# RaspberyConnector.net
KiCad netlist of a schematic drawn in Altium Designer
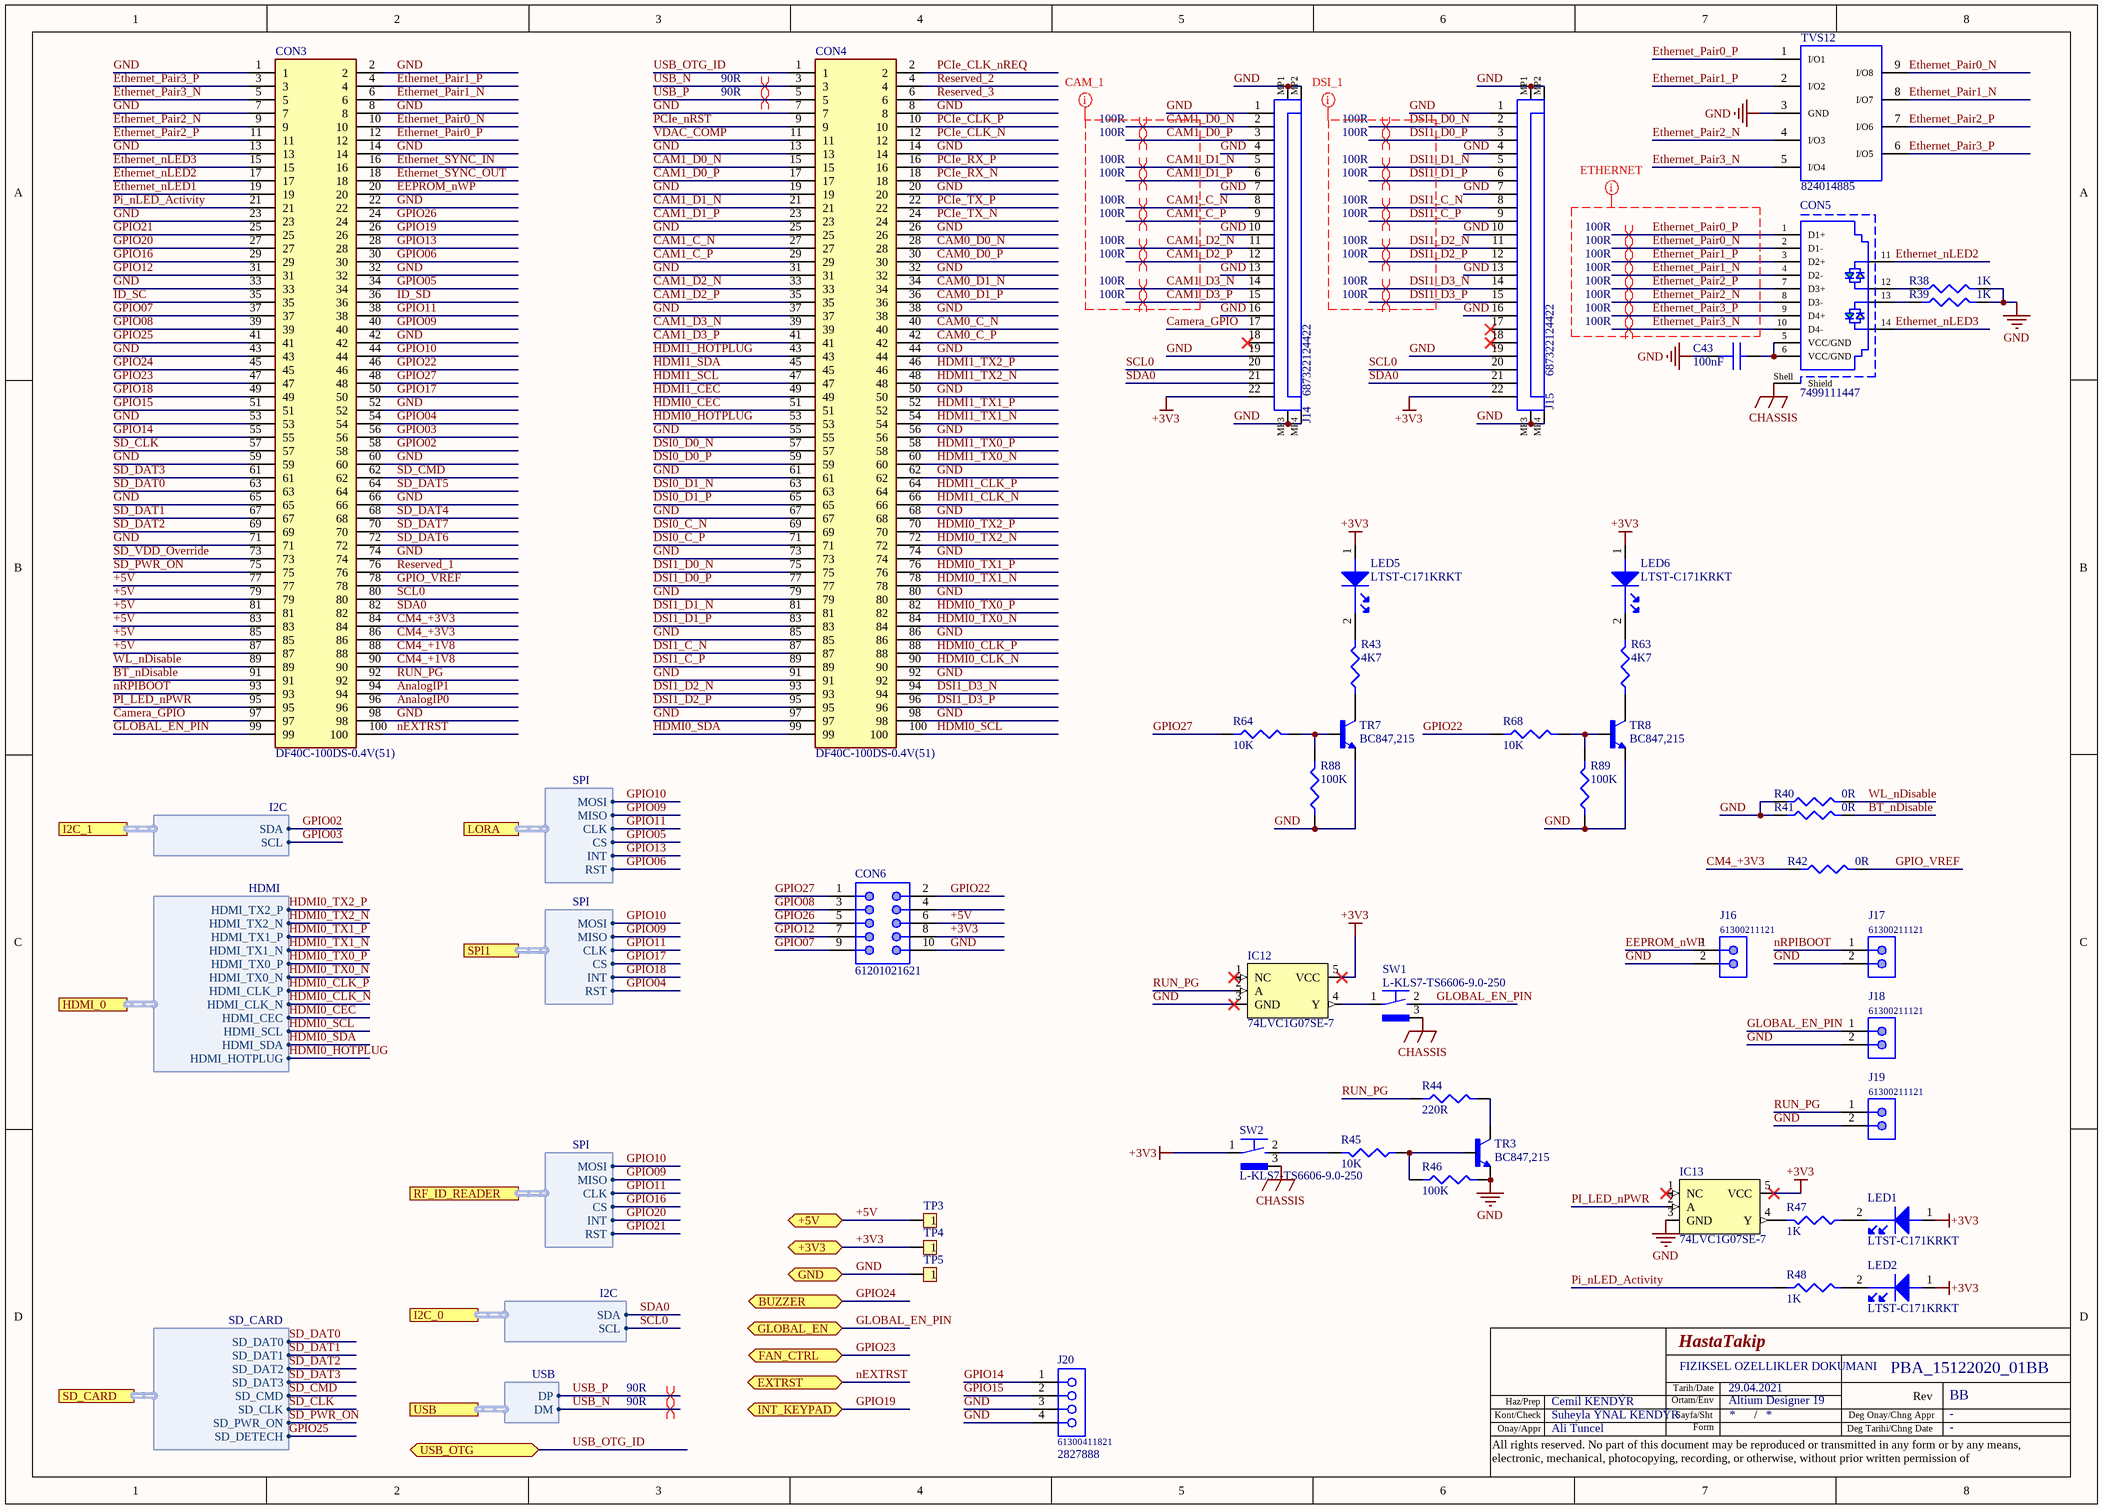
[diagram p0: RaspberyConnector.SchDoc]

(export (version "E")
  (design (tool "Eeschema 10.0.6"))
  (components
    (comp (ref "C43")
      (value "100nF")
      (footprint "C0603")
      (description "100nF, 25V, X7R, 10%, 0603")
      (fields
        (field (name "MANUFACTURER") "Yageo")
        (field (name "MANUFACTURER PART NUMBER") "CC0603KRX7R8BB104")
      )
      (libsource (lib "McmLibrary") (part "CC0603KRX7R8BB104"))
    )
    (comp (ref "CON3")
      (value "DF40C-100DS-0.4V(51)")
      (footprint "HRS_DF40C-100DS-0.4V(51)")
      (fields (field (name "MANUFACTURER") "Hirose"))
      (libsource (lib "McmLibrary") (part "DF40C-100DS-0.4V(51)"))
    )
    (comp (ref "CON4")
      (value "DF40C-100DS-0.4V(51)")
      (footprint "HRS_DF40C-100DS-0.4V(51)")
      (fields (field (name "MANUFACTURER") "Hirose"))
      (libsource (lib "McmLibrary") (part "DF40C-100DS-0.4V(51)"))
    )
    (comp (ref "CON5")
      (value "7499111447")
      (footprint "7499111447")
      (description "WURTH ELEKTRONIK - 7499111447 - MODULAR JACK, RJ45, 1000 BASE, 1PORT")
      (fields (field (name "MANUFACTURER") "Wurth Electronics"))
      (libsource (lib "McmLibrary") (part "7499111447"))
    )
    (comp (ref "CON6")
      (value "61201021621")
      (footprint "61201021621")
      (fields (field (name "MANUFACTURER") "Wurth Electronics"))
      (libsource (lib "McmLibrary") (part "61201021621"))
    )
    (comp (ref "IC12")
      (value "74LVC1G07SE-7")
      (footprint "SOT353")
      (description "Buffer/Driver 1-CH Non-Inverting Open Drain CMOS 5-Pin SOT-353 T/R")
      (fields (field (name "MANUFACTURER") "Diodes"))
      (libsource (lib "InterfaceDriversReceiversTransceivers") (part "74LVC1G07SE-7"))
    )
    (comp (ref "IC13")
      (value "74LVC1G07SE-7")
      (footprint "SOT353")
      (description "Buffer/Driver 1-CH Non-Inverting Open Drain CMOS 5-Pin SOT-353 T/R")
      (fields (field (name "MANUFACTURER") "Diodes"))
      (libsource (lib "InterfaceDriversReceiversTransceivers") (part "74LVC1G07SE-7"))
    )
    (comp (ref "J14")
      (value "687322124422")
      (footprint "687322124422")
      (description "WR-FPC SMT ZIF Vertical, pitch 0.5mm, 22p")
      (fields (field (name "MANUFACTURER") "Wurth Elektronik") (field (name "PUBLISHER") "Wurth Elektronik"))
      (libsource (lib "Connectors") (part "687322124422"))
    )
    (comp (ref "J15")
      (value "687322124422")
      (footprint "687322124422")
      (description "WR-FPC SMT ZIF Vertical, pitch 0.5mm, 22p")
      (fields (field (name "MANUFACTURER") "Wurth Elektronik") (field (name "PUBLISHER") "Wurth Elektronik"))
      (libsource (lib "Connectors") (part "687322124422"))
    )
    (comp (ref "J16")
      (value "61300211121")
      (footprint "61300211121")
      (description "WR-PHD Pin Header, THT, pitch 2.54mm, Single Row, Vertical, 2pin")
      (fields (field (name "MANUFACTURER") "Wurth Electronics") (field (name "PUBLISHER") "Wurth Elektronik"))
      (libsource (lib "McmLibrary") (part "61300211121"))
    )
    (comp (ref "J17")
      (value "61300211121")
      (footprint "61300211121")
      (description "WR-PHD Pin Header, THT, pitch 2.54mm, Single Row, Vertical, 2pin")
      (fields (field (name "MANUFACTURER") "Wurth Electronics") (field (name "PUBLISHER") "Wurth Elektronik"))
      (libsource (lib "McmLibrary") (part "61300211121"))
    )
    (comp (ref "J18")
      (value "61300211121")
      (footprint "61300211121")
      (description "WR-PHD Pin Header, THT, pitch 2.54mm, Single Row, Vertical, 2pin")
      (fields (field (name "MANUFACTURER") "Wurth Electronics") (field (name "PUBLISHER") "Wurth Elektronik"))
      (libsource (lib "McmLibrary") (part "61300211121"))
    )
    (comp (ref "J19")
      (value "61300211121")
      (footprint "61300211121")
      (description "WR-PHD Pin Header, THT, pitch 2.54mm, Single Row, Vertical, 2pin")
      (fields (field (name "MANUFACTURER") "Wurth Electronics") (field (name "PUBLISHER") "Wurth Elektronik"))
      (libsource (lib "McmLibrary") (part "61300211121"))
    )
    (comp (ref "J20")
      (value "61300411821")
      (footprint "61300411821")
      (description "WR-PHD Socket Header, THT, pitch 2.54mm, Single Row, Vertical, 4pin")
      (fields
        (field (name "MANUFACTURER") "Wurth Electronics")
        (field (name "SUPPLIER PART NUMBER 1") "2827888")
        (field (name "PUBLISHER") "Wurth Elektronik")
      )
      (libsource (lib "PinHeaders") (part "61300411821"))
    )
    (comp (ref "LED1")
      (value "LTST-C171KRKT")
      (footprint "0805_RED")
      (description "LED RED CLEAR SMD")
      (fields (field (name "MANUFACTURER") "Vishay Lite-On"))
      (libsource (lib "McmLibrary") (part "LTST-C171KRKT"))
    )
    (comp (ref "LED2")
      (value "LTST-C171KRKT")
      (footprint "0805_RED")
      (description "LED RED CLEAR SMD")
      (fields (field (name "MANUFACTURER") "Vishay Lite-On"))
      (libsource (lib "McmLibrary") (part "LTST-C171KRKT"))
    )
    (comp (ref "LED5")
      (value "LTST-C171KRKT")
      (footprint "0805_RED")
      (description "LED RED CLEAR SMD")
      (fields (field (name "MANUFACTURER") "Vishay Lite-On"))
      (libsource (lib "McmLibrary") (part "LTST-C171KRKT"))
    )
    (comp (ref "LED6")
      (value "LTST-C171KRKT")
      (footprint "0805_RED")
      (description "LED RED CLEAR SMD")
      (fields (field (name "MANUFACTURER") "Vishay Lite-On"))
      (libsource (lib "McmLibrary") (part "LTST-C171KRKT"))
    )
    (comp (ref "R38")
      (value "1K")
      (footprint "R0603")
      (description "1K ,%1 ,1/10 W ,0603")
      (fields
        (field (name "MANUFACTURER") "Yageo")
        (field (name "MANUFACTURER PART NUMBER") "RC0603FR-071KL")
      )
      (libsource (lib "McmLibrary") (part "RC0603FR-071KL"))
    )
    (comp (ref "R39")
      (value "1K")
      (footprint "R0603")
      (description "1K ,%1 ,1/10 W ,0603")
      (fields
        (field (name "MANUFACTURER") "Yageo")
        (field (name "MANUFACTURER PART NUMBER") "RC0603FR-071KL")
      )
      (libsource (lib "McmLibrary") (part "RC0603FR-071KL"))
    )
    (comp (ref "R40")
      (value "0R")
      (footprint "R0603")
      (description "0R ,%1 ,1/10 W ,0603")
      (fields
        (field (name "MANUFACTURER") "Yageo")
        (field (name "MANUFACTURER PART NUMBER") "RC0603FR-070RL")
      )
      (libsource (lib "McmLibrary") (part "RC0603FR-070RL"))
    )
    (comp (ref "R41")
      (value "0R")
      (footprint "R0603")
      (description "0R ,%1 ,1/10 W ,0603")
      (fields
        (field (name "MANUFACTURER") "Yageo")
        (field (name "MANUFACTURER PART NUMBER") "RC0603FR-070RL")
      )
      (libsource (lib "McmLibrary") (part "RC0603FR-070RL"))
    )
    (comp (ref "R42")
      (value "0R")
      (footprint "R0603")
      (description "0R ,%1 ,1/10 W ,0603")
      (fields
        (field (name "MANUFACTURER") "Yageo")
        (field (name "MANUFACTURER PART NUMBER") "RC0603FR-070RL")
      )
      (libsource (lib "McmLibrary") (part "RC0603FR-070RL"))
    )
    (comp (ref "R43")
      (value "4K7")
      (footprint "R0603")
      (description "4.7K OHM 1% 1/10W 0603")
      (fields
        (field (name "MANUFACTURER") "Yageo")
        (field (name "MANUFACTURER PART NUMBER") "RC0603FR-074K7L")
      )
      (libsource (lib "McmLibrary") (part "RC0603FR-074K7L"))
    )
    (comp (ref "R44")
      (value "220R")
      (footprint "R0603")
      (description "220 R, %1, 1/10W, 0603")
      (fields
        (field (name "MANUFACTURER") "Yageo")
        (field (name "MANUFACTURER PART NUMBER") "RC0603FR-07220RL")
      )
      (libsource (lib "McmLibrary") (part "RC0603FR-07220RL"))
    )
    (comp (ref "R45")
      (value "10K")
      (footprint "R0603")
      (description "10K OHM 1% 1/10W 0603")
      (fields
        (field (name "MANUFACTURER") "Yageo")
        (field (name "MANUFACTURER PART NUMBER") "RT0603FRE0710KL")
      )
      (libsource (lib "McmLibrary") (part "RT0603FRE0710KL"))
    )
    (comp (ref "R46")
      (value "100K")
      (footprint "R0603")
      (description "100K ,%1 ,1/10 W ,0603")
      (fields
        (field (name "MANUFACTURER") "Yageo")
        (field (name "MANUFACTURER PART NUMBER") "RC0603FR-07100KL")
      )
      (libsource (lib "McmLibrary") (part "RC0603FR-07100KL"))
    )
    (comp (ref "R47")
      (value "1K")
      (footprint "R0603")
      (description "1K ,%1 ,1/10 W ,0603")
      (fields
        (field (name "MANUFACTURER") "Yageo")
        (field (name "MANUFACTURER PART NUMBER") "RC0603FR-071KL")
      )
      (libsource (lib "McmLibrary") (part "RC0603FR-071KL"))
    )
    (comp (ref "R48")
      (value "1K")
      (footprint "R0603")
      (description "1K ,%1 ,1/10 W ,0603")
      (fields
        (field (name "MANUFACTURER") "Yageo")
        (field (name "MANUFACTURER PART NUMBER") "RC0603FR-071KL")
      )
      (libsource (lib "McmLibrary") (part "RC0603FR-071KL"))
    )
    (comp (ref "R63")
      (value "4K7")
      (footprint "R0603")
      (description "4.7K OHM 1% 1/10W 0603")
      (fields
        (field (name "MANUFACTURER") "Yageo")
        (field (name "MANUFACTURER PART NUMBER") "RC0603FR-074K7L")
      )
      (libsource (lib "McmLibrary") (part "RC0603FR-074K7L"))
    )
    (comp (ref "R64")
      (value "10K")
      (footprint "R0603")
      (description "10K OHM 1% 1/10W 0603")
      (fields
        (field (name "MANUFACTURER") "Yageo")
        (field (name "MANUFACTURER PART NUMBER") "RT0603FRE0710KL")
      )
      (libsource (lib "McmLibrary") (part "RT0603FRE0710KL"))
    )
    (comp (ref "R68")
      (value "10K")
      (footprint "R0603")
      (description "10K OHM 1% 1/10W 0603")
      (fields
        (field (name "MANUFACTURER") "Yageo")
        (field (name "MANUFACTURER PART NUMBER") "RT0603FRE0710KL")
      )
      (libsource (lib "McmLibrary") (part "RT0603FRE0710KL"))
    )
    (comp (ref "R88")
      (value "100K")
      (footprint "R0603")
      (description "100K Ohm 1% 1/10W 0603")
      (fields
        (field (name "MANUFACTURER") "Yageo")
        (field (name "MANUFACTURER PART NUMBER") "RC0603FR-07100KL")
      )
      (libsource (lib "McmLibrary") (part "RC0603FR-07100KL"))
    )
    (comp (ref "R89")
      (value "100K")
      (footprint "R0603")
      (description "100K Ohm 1% 1/10W 0603")
      (fields
        (field (name "MANUFACTURER") "Yageo")
        (field (name "MANUFACTURER PART NUMBER") "RC0603FR-07100KL")
      )
      (libsource (lib "McmLibrary") (part "RC0603FR-07100KL"))
    )
    (comp (ref "SW1")
      (value "L-KLS7-TS6606-9.0-250")
      (footprint "Right angle 9mm")
      (description "Right angle 6X6X9mm")
      (libsource (lib "Switch") (part "L-KLS7-TS6606-9.0-250"))
    )
    (comp (ref "SW2")
      (value "L-KLS7-TS6606-9.0-250")
      (footprint "Right angle 9mm")
      (description "Right angle 6X6X9mm")
      (libsource (lib "Switch") (part "L-KLS7-TS6606-9.0-250"))
    )
    (comp (ref "TP3")
      (value "TestPoint1")
      (footprint "SMD_2mmPoint")
      (description "test ölçüm noktası")
      (libsource (lib "McmLibrary") (part "TestPoint1"))
    )
    (comp (ref "TP4")
      (value "TestPoint1")
      (footprint "SMD_2mmPoint")
      (description "test ölçüm noktası")
      (libsource (lib "McmLibrary") (part "TestPoint1"))
    )
    (comp (ref "TP5")
      (value "TestPoint1")
      (footprint "SMD_2mmPoint")
      (description "test ölçüm noktası")
      (libsource (lib "McmLibrary") (part "TestPoint1"))
    )
    (comp (ref "TR3")
      (value "BC847,215")
      (footprint "SOT23")
      (description "TRANS NPN 45V 0.1A SOT23")
      (fields (field (name "MANUFACTURER") "Nexperia"))
      (libsource (lib "McmLibrary") (part "BC847,215"))
    )
    (comp (ref "TR7")
      (value "BC847,215")
      (footprint "SOT23")
      (description "TRANS NPN 45V 0.1A SOT23")
      (fields (field (name "MANUFACTURER") "Nexperia"))
      (libsource (lib "McmLibrary") (part "BC847,215"))
    )
    (comp (ref "TR8")
      (value "BC847,215")
      (footprint "SOT23")
      (description "TRANS NPN 45V 0.1A SOT23")
      (fields (field (name "MANUFACTURER") "Nexperia"))
      (libsource (lib "McmLibrary") (part "BC847,215"))
    )
    (comp (ref "TVS12")
      (value "824014885")
      (footprint "WE-TVS_DFN3810-9L")
      (description "TVS DIODE 5V 10.5V DFN3810-9")
      (fields (field (name "MANUFACTURER") "Wurth Electronics"))
      (libsource (lib "TVS") (part "824014885"))
    )
  )
  (nets
    (net (code "6") (name "+3V3") (class "Default")
      (node (ref "CON6") (pin "8") (pinfunction "8_8") (pintype "passive"))
      (node (ref "IC12") (pin "5") (pinfunction "VCC_5") (pintype "power_in"))
      (node (ref "IC13") (pin "5") (pinfunction "VCC_5") (pintype "power_in"))
      (node (ref "J14") (pin "22") (pinfunction "22_22") (pintype "passive"))
      (node (ref "J15") (pin "22") (pinfunction "22_22") (pintype "passive"))
      (node (ref "LED1") (pin "1") (pinfunction "1_1") (pintype "passive"))
      (node (ref "LED2") (pin "1") (pinfunction "1_1") (pintype "passive"))
      (node (ref "LED5") (pin "1") (pinfunction "1_1") (pintype "passive"))
      (node (ref "LED6") (pin "1") (pinfunction "1_1") (pintype "passive"))
      (node (ref "SW2") (pin "1") (pinfunction "1_1") (pintype "passive"))
      (node (ref "TP4") (pin "1") (pinfunction "1_1") (pintype "passive"))
    )
    (net (code "7") (name "/+5V") (class "Default")
      (node (ref "CON3") (pin "77") (pinfunction "77_77") (pintype "passive"))
      (node (ref "CON3") (pin "79") (pinfunction "79_79") (pintype "passive"))
      (node (ref "CON3") (pin "81") (pinfunction "81_81") (pintype "passive"))
      (node (ref "CON3") (pin "83") (pinfunction "83_83") (pintype "passive"))
      (node (ref "CON3") (pin "85") (pinfunction "85_85") (pintype "passive"))
      (node (ref "CON3") (pin "87") (pinfunction "87_87") (pintype "passive"))
      (node (ref "CON6") (pin "6") (pinfunction "6_6") (pintype "passive"))
      (node (ref "TP3") (pin "1") (pinfunction "1_1") (pintype "passive"))
    )
    (net (code "8") (name "/AnalogIP0") (class "Default")
      (node (ref "CON3") (pin "96") (pinfunction "96_96") (pintype "passive"))
    )
    (net (code "9") (name "/AnalogIP1") (class "Default")
      (node (ref "CON3") (pin "94") (pinfunction "94_94") (pintype "passive"))
    )
    (net (code "10") (name "/BT_nDisable") (class "Default")
      (node (ref "CON3") (pin "91") (pinfunction "91_91") (pintype "passive"))
      (node (ref "R41") (pin "2") (pinfunction "2_2") (pintype "passive"))
    )
    (net (code "11") (name "/CAM0_C_N") (class "Default")
      (node (ref "CON4") (pin "40") (pinfunction "40_40") (pintype "passive"))
    )
    (net (code "12") (name "/CAM0_C_P") (class "Default")
      (node (ref "CON4") (pin "42") (pinfunction "42_42") (pintype "passive"))
    )
    (net (code "13") (name "/CAM0_D0_N") (class "Default")
      (node (ref "CON4") (pin "28") (pinfunction "28_28") (pintype "passive"))
    )
    (net (code "14") (name "/CAM0_D0_P") (class "Default")
      (node (ref "CON4") (pin "30") (pinfunction "30_30") (pintype "passive"))
    )
    (net (code "15") (name "/CAM0_D1_N") (class "Default")
      (node (ref "CON4") (pin "34") (pinfunction "34_34") (pintype "passive"))
    )
    (net (code "16") (name "/CAM0_D1_P") (class "Default")
      (node (ref "CON4") (pin "36") (pinfunction "36_36") (pintype "passive"))
    )
    (net (code "17") (name "/CAM1_C_N") (class "Default")
      (node (ref "CON4") (pin "27") (pinfunction "27_27") (pintype "passive"))
      (node (ref "J14") (pin "8") (pinfunction "8_8") (pintype "passive"))
    )
    (net (code "18") (name "/CAM1_C_P") (class "Default")
      (node (ref "CON4") (pin "29") (pinfunction "29_29") (pintype "passive"))
      (node (ref "J14") (pin "9") (pinfunction "9_9") (pintype "passive"))
    )
    (net (code "19") (name "/CAM1_D0_N") (class "Default")
      (node (ref "CON4") (pin "15") (pinfunction "15_15") (pintype "passive"))
      (node (ref "J14") (pin "2") (pinfunction "2_2") (pintype "passive"))
    )
    (net (code "20") (name "/CAM1_D0_P") (class "Default")
      (node (ref "CON4") (pin "17") (pinfunction "17_17") (pintype "passive"))
      (node (ref "J14") (pin "3") (pinfunction "3_3") (pintype "passive"))
    )
    (net (code "21") (name "/CAM1_D1_N") (class "Default")
      (node (ref "CON4") (pin "21") (pinfunction "21_21") (pintype "passive"))
      (node (ref "J14") (pin "5") (pinfunction "5_5") (pintype "passive"))
    )
    (net (code "22") (name "/CAM1_D1_P") (class "Default")
      (node (ref "CON4") (pin "23") (pinfunction "23_23") (pintype "passive"))
      (node (ref "J14") (pin "6") (pinfunction "6_6") (pintype "passive"))
    )
    (net (code "23") (name "/CAM1_D2_N") (class "Default")
      (node (ref "CON4") (pin "33") (pinfunction "33_33") (pintype "passive"))
      (node (ref "J14") (pin "11") (pinfunction "11_11") (pintype "passive"))
    )
    (net (code "24") (name "/CAM1_D2_P") (class "Default")
      (node (ref "CON4") (pin "35") (pinfunction "35_35") (pintype "passive"))
      (node (ref "J14") (pin "12") (pinfunction "12_12") (pintype "passive"))
    )
    (net (code "25") (name "/CAM1_D3_N") (class "Default")
      (node (ref "CON4") (pin "39") (pinfunction "39_39") (pintype "passive"))
      (node (ref "J14") (pin "14") (pinfunction "14_14") (pintype "passive"))
    )
    (net (code "26") (name "/CAM1_D3_P") (class "Default")
      (node (ref "CON4") (pin "41") (pinfunction "41_41") (pintype "passive"))
      (node (ref "J14") (pin "15") (pinfunction "15_15") (pintype "passive"))
    )
    (net (code "27") (name "/CM4_+1V8") (class "Default")
      (node (ref "CON3") (pin "88") (pinfunction "88_88") (pintype "passive"))
      (node (ref "CON3") (pin "90") (pinfunction "90_90") (pintype "passive"))
    )
    (net (code "28") (name "/CM4_+3V3") (class "Default")
      (node (ref "CON3") (pin "84") (pinfunction "84_84") (pintype "passive"))
      (node (ref "CON3") (pin "86") (pinfunction "86_86") (pintype "passive"))
      (node (ref "R42") (pin "1") (pinfunction "1_1") (pintype "passive"))
    )
    (net (code "29") (name "/Camera_GPIO") (class "Default")
      (node (ref "CON3") (pin "97") (pinfunction "97_97") (pintype "passive"))
      (node (ref "J14") (pin "17") (pinfunction "17_17") (pintype "passive"))
    )
    (net (code "30") (name "/DSI0_C_N") (class "Default")
      (node (ref "CON4") (pin "69") (pinfunction "69_69") (pintype "passive"))
    )
    (net (code "31") (name "/DSI0_C_P") (class "Default")
      (node (ref "CON4") (pin "71") (pinfunction "71_71") (pintype "passive"))
    )
    (net (code "32") (name "/DSI0_D0_N") (class "Default")
      (node (ref "CON4") (pin "57") (pinfunction "57_57") (pintype "passive"))
    )
    (net (code "33") (name "/DSI0_D0_P") (class "Default")
      (node (ref "CON4") (pin "59") (pinfunction "59_59") (pintype "passive"))
    )
    (net (code "34") (name "/DSI0_D1_N") (class "Default")
      (node (ref "CON4") (pin "63") (pinfunction "63_63") (pintype "passive"))
    )
    (net (code "35") (name "/DSI0_D1_P") (class "Default")
      (node (ref "CON4") (pin "65") (pinfunction "65_65") (pintype "passive"))
    )
    (net (code "36") (name "/DSI1_C_N") (class "Default")
      (node (ref "CON4") (pin "87") (pinfunction "87_87") (pintype "passive"))
      (node (ref "J15") (pin "8") (pinfunction "8_8") (pintype "passive"))
    )
    (net (code "37") (name "/DSI1_C_P") (class "Default")
      (node (ref "CON4") (pin "89") (pinfunction "89_89") (pintype "passive"))
      (node (ref "J15") (pin "9") (pinfunction "9_9") (pintype "passive"))
    )
    (net (code "38") (name "/DSI1_D0_N") (class "Default")
      (node (ref "CON4") (pin "75") (pinfunction "75_75") (pintype "passive"))
      (node (ref "J15") (pin "2") (pinfunction "2_2") (pintype "passive"))
    )
    (net (code "39") (name "/DSI1_D0_P") (class "Default")
      (node (ref "CON4") (pin "77") (pinfunction "77_77") (pintype "passive"))
      (node (ref "J15") (pin "3") (pinfunction "3_3") (pintype "passive"))
    )
    (net (code "40") (name "/DSI1_D1_N") (class "Default")
      (node (ref "CON4") (pin "81") (pinfunction "81_81") (pintype "passive"))
      (node (ref "J15") (pin "5") (pinfunction "5_5") (pintype "passive"))
    )
    (net (code "41") (name "/DSI1_D1_P") (class "Default")
      (node (ref "CON4") (pin "83") (pinfunction "83_83") (pintype "passive"))
      (node (ref "J15") (pin "6") (pinfunction "6_6") (pintype "passive"))
    )
    (net (code "42") (name "/DSI1_D2_N") (class "Default")
      (node (ref "CON4") (pin "93") (pinfunction "93_93") (pintype "passive"))
      (node (ref "J15") (pin "11") (pinfunction "11_11") (pintype "passive"))
    )
    (net (code "43") (name "/DSI1_D2_P") (class "Default")
      (node (ref "CON4") (pin "95") (pinfunction "95_95") (pintype "passive"))
      (node (ref "J15") (pin "12") (pinfunction "12_12") (pintype "passive"))
    )
    (net (code "44") (name "/DSI1_D3_N") (class "Default")
      (node (ref "CON4") (pin "94") (pinfunction "94_94") (pintype "passive"))
      (node (ref "J15") (pin "14") (pinfunction "14_14") (pintype "passive"))
    )
    (net (code "45") (name "/DSI1_D3_P") (class "Default")
      (node (ref "CON4") (pin "96") (pinfunction "96_96") (pintype "passive"))
      (node (ref "J15") (pin "15") (pinfunction "15_15") (pintype "passive"))
    )
    (net (code "46") (name "/EEPROM_nWP") (class "Default")
      (node (ref "CON3") (pin "20") (pinfunction "20_20") (pintype "passive"))
      (node (ref "J16") (pin "1") (pinfunction "1_1") (pintype "passive"))
    )
    (net (code "47") (name "/Ethernet_Pair0_N") (class "Default")
      (node (ref "CON3") (pin "10") (pinfunction "10_10") (pintype "passive"))
      (node (ref "CON5") (pin "2") (pinfunction "D1-_2") (pintype "passive"))
      (node (ref "TVS12") (pin "9") (pinfunction "I/O8_9") (pintype "passive"))
    )
    (net (code "48") (name "/Ethernet_Pair0_P") (class "Default")
      (node (ref "CON3") (pin "12") (pinfunction "12_12") (pintype "passive"))
      (node (ref "CON5") (pin "1") (pinfunction "D1+_1") (pintype "passive"))
      (node (ref "TVS12") (pin "1") (pinfunction "I/O1_1") (pintype "passive"))
    )
    (net (code "49") (name "/Ethernet_Pair1_N") (class "Default")
      (node (ref "CON3") (pin "6") (pinfunction "6_6") (pintype "passive"))
      (node (ref "CON5") (pin "4") (pinfunction "D2-_4") (pintype "passive"))
      (node (ref "TVS12") (pin "8") (pinfunction "I/O7_8") (pintype "passive"))
    )
    (net (code "50") (name "/Ethernet_Pair1_P") (class "Default")
      (node (ref "CON3") (pin "4") (pinfunction "4_4") (pintype "passive"))
      (node (ref "CON5") (pin "3") (pinfunction "D2+_3") (pintype "passive"))
      (node (ref "TVS12") (pin "2") (pinfunction "I/O2_2") (pintype "passive"))
    )
    (net (code "51") (name "/Ethernet_Pair2_N") (class "Default")
      (node (ref "CON3") (pin "9") (pinfunction "9_9") (pintype "passive"))
      (node (ref "CON5") (pin "8") (pinfunction "D3-_8") (pintype "passive"))
      (node (ref "TVS12") (pin "4") (pinfunction "I/O3_4") (pintype "passive"))
    )
    (net (code "52") (name "/Ethernet_Pair2_P") (class "Default")
      (node (ref "CON3") (pin "11") (pinfunction "11_11") (pintype "passive"))
      (node (ref "CON5") (pin "7") (pinfunction "D3+_7") (pintype "passive"))
      (node (ref "TVS12") (pin "7") (pinfunction "I/O6_7") (pintype "passive"))
    )
    (net (code "53") (name "/Ethernet_Pair3_N") (class "Default")
      (node (ref "CON3") (pin "5") (pinfunction "5_5") (pintype "passive"))
      (node (ref "CON5") (pin "10") (pinfunction "D4-_10") (pintype "passive"))
      (node (ref "TVS12") (pin "5") (pinfunction "I/O4_5") (pintype "passive"))
    )
    (net (code "54") (name "/Ethernet_Pair3_P") (class "Default")
      (node (ref "CON3") (pin "3") (pinfunction "3_3") (pintype "passive"))
      (node (ref "CON5") (pin "9") (pinfunction "D4+_9") (pintype "passive"))
      (node (ref "TVS12") (pin "6") (pinfunction "I/O5_6") (pintype "passive"))
    )
    (net (code "55") (name "/Ethernet_SYNC_IN") (class "Default")
      (node (ref "CON3") (pin "16") (pinfunction "16_16") (pintype "passive"))
    )
    (net (code "56") (name "/Ethernet_SYNC_OUT") (class "Default")
      (node (ref "CON3") (pin "18") (pinfunction "18_18") (pintype "passive"))
    )
    (net (code "57") (name "/Ethernet_nLED1") (class "Default")
      (node (ref "CON3") (pin "19") (pinfunction "19_19") (pintype "passive"))
    )
    (net (code "58") (name "/Ethernet_nLED2") (class "Default")
      (node (ref "CON3") (pin "17") (pinfunction "17_17") (pintype "passive"))
      (node (ref "CON5") (pin "11") (pinfunction "11_11") (pintype "passive"))
    )
    (net (code "59") (name "/Ethernet_nLED3") (class "Default")
      (node (ref "CON3") (pin "15") (pinfunction "15_15") (pintype "passive"))
      (node (ref "CON5") (pin "14") (pinfunction "14_14") (pintype "passive"))
    )
    (net (code "60") (name "/GLOBAL_EN_PIN") (class "Default")
      (node (ref "CON3") (pin "99") (pinfunction "99_99") (pintype "passive"))
      (node (ref "J18") (pin "1") (pinfunction "1_1") (pintype "passive"))
      (node (ref "SW1") (pin "2") (pinfunction "2_2") (pintype "passive"))
    )
    (net (code "61") (name "/GPIO02") (class "Default")
      (node (ref "CON3") (pin "58") (pinfunction "58_58") (pintype "passive"))
    )
    (net (code "62") (name "/GPIO03") (class "Default")
      (node (ref "CON3") (pin "56") (pinfunction "56_56") (pintype "passive"))
    )
    (net (code "63") (name "/GPIO04") (class "Default")
      (node (ref "CON3") (pin "54") (pinfunction "54_54") (pintype "passive"))
    )
    (net (code "64") (name "/GPIO05") (class "Default")
      (node (ref "CON3") (pin "34") (pinfunction "34_34") (pintype "passive"))
    )
    (net (code "65") (name "/GPIO06") (class "Default")
      (node (ref "CON3") (pin "30") (pinfunction "30_30") (pintype "passive"))
    )
    (net (code "66") (name "/GPIO07") (class "Default")
      (node (ref "CON3") (pin "37") (pinfunction "37_37") (pintype "passive"))
      (node (ref "CON6") (pin "9") (pinfunction "9_9") (pintype "passive"))
    )
    (net (code "67") (name "/GPIO08") (class "Default")
      (node (ref "CON3") (pin "39") (pinfunction "39_39") (pintype "passive"))
      (node (ref "CON6") (pin "3") (pinfunction "3_3") (pintype "passive"))
    )
    (net (code "68") (name "/GPIO09") (class "Default")
      (node (ref "CON3") (pin "40") (pinfunction "40_40") (pintype "passive"))
    )
    (net (code "69") (name "/GPIO10") (class "Default")
      (node (ref "CON3") (pin "44") (pinfunction "44_44") (pintype "passive"))
    )
    (net (code "70") (name "/GPIO11") (class "Default")
      (node (ref "CON3") (pin "38") (pinfunction "38_38") (pintype "passive"))
    )
    (net (code "71") (name "/GPIO12") (class "Default")
      (node (ref "CON3") (pin "31") (pinfunction "31_31") (pintype "passive"))
      (node (ref "CON6") (pin "7") (pinfunction "7_7") (pintype "passive"))
    )
    (net (code "72") (name "/GPIO13") (class "Default")
      (node (ref "CON3") (pin "28") (pinfunction "28_28") (pintype "passive"))
    )
    (net (code "73") (name "/GPIO14") (class "Default")
      (node (ref "CON3") (pin "55") (pinfunction "55_55") (pintype "passive"))
      (node (ref "J20") (pin "1") (pinfunction "1_1") (pintype "passive"))
    )
    (net (code "74") (name "/GPIO15") (class "Default")
      (node (ref "CON3") (pin "51") (pinfunction "51_51") (pintype "passive"))
      (node (ref "J20") (pin "2") (pinfunction "2_2") (pintype "passive"))
    )
    (net (code "75") (name "/GPIO16") (class "Default")
      (node (ref "CON3") (pin "29") (pinfunction "29_29") (pintype "passive"))
    )
    (net (code "76") (name "/GPIO17") (class "Default")
      (node (ref "CON3") (pin "50") (pinfunction "50_50") (pintype "passive"))
    )
    (net (code "77") (name "/GPIO18") (class "Default")
      (node (ref "CON3") (pin "49") (pinfunction "49_49") (pintype "passive"))
    )
    (net (code "78") (name "/GPIO19") (class "Default")
      (node (ref "CON3") (pin "26") (pinfunction "26_26") (pintype "passive"))
    )
    (net (code "79") (name "/GPIO20") (class "Default")
      (node (ref "CON3") (pin "27") (pinfunction "27_27") (pintype "passive"))
    )
    (net (code "80") (name "/GPIO21") (class "Default")
      (node (ref "CON3") (pin "25") (pinfunction "25_25") (pintype "passive"))
    )
    (net (code "81") (name "/GPIO22") (class "Default")
      (node (ref "CON3") (pin "46") (pinfunction "46_46") (pintype "passive"))
      (node (ref "CON6") (pin "2") (pinfunction "2_2") (pintype "passive"))
      (node (ref "R68") (pin "1") (pinfunction "1_1") (pintype "passive"))
    )
    (net (code "82") (name "/GPIO23") (class "Default")
      (node (ref "CON3") (pin "47") (pinfunction "47_47") (pintype "passive"))
    )
    (net (code "83") (name "/GPIO24") (class "Default")
      (node (ref "CON3") (pin "45") (pinfunction "45_45") (pintype "passive"))
    )
    (net (code "84") (name "/GPIO25") (class "Default")
      (node (ref "CON3") (pin "41") (pinfunction "41_41") (pintype "passive"))
    )
    (net (code "85") (name "/GPIO26") (class "Default")
      (node (ref "CON3") (pin "24") (pinfunction "24_24") (pintype "passive"))
      (node (ref "CON6") (pin "5") (pinfunction "5_5") (pintype "passive"))
    )
    (net (code "86") (name "/GPIO27") (class "Default")
      (node (ref "CON3") (pin "48") (pinfunction "48_48") (pintype "passive"))
      (node (ref "CON6") (pin "1") (pinfunction "1_1") (pintype "passive"))
      (node (ref "R64") (pin "1") (pinfunction "1_1") (pintype "passive"))
    )
    (net (code "87") (name "/GPIO_VREF") (class "Default")
      (node (ref "CON3") (pin "78") (pinfunction "78_78") (pintype "passive"))
      (node (ref "R42") (pin "2") (pinfunction "2_2") (pintype "passive"))
    )
    (net (code "88") (name "/HDMI0_CEC") (class "Default")
      (node (ref "CON4") (pin "51") (pinfunction "51_51") (pintype "passive"))
    )
    (net (code "89") (name "/HDMI0_CLK_N") (class "Default")
      (node (ref "CON4") (pin "90") (pinfunction "90_90") (pintype "passive"))
    )
    (net (code "90") (name "/HDMI0_CLK_P") (class "Default")
      (node (ref "CON4") (pin "88") (pinfunction "88_88") (pintype "passive"))
    )
    (net (code "91") (name "/HDMI0_HOTPLUG") (class "Default")
      (node (ref "CON4") (pin "53") (pinfunction "53_53") (pintype "passive"))
    )
    (net (code "92") (name "/HDMI0_SCL") (class "Default")
      (node (ref "CON4") (pin "100") (pinfunction "100_100") (pintype "passive"))
    )
    (net (code "93") (name "/HDMI0_SDA") (class "Default")
      (node (ref "CON4") (pin "99") (pinfunction "99_99") (pintype "passive"))
    )
    (net (code "94") (name "/HDMI0_TX0_N") (class "Default")
      (node (ref "CON4") (pin "84") (pinfunction "84_84") (pintype "passive"))
    )
    (net (code "95") (name "/HDMI0_TX0_P") (class "Default")
      (node (ref "CON4") (pin "82") (pinfunction "82_82") (pintype "passive"))
    )
    (net (code "96") (name "/HDMI0_TX1_N") (class "Default")
      (node (ref "CON4") (pin "78") (pinfunction "78_78") (pintype "passive"))
    )
    (net (code "97") (name "/HDMI0_TX1_P") (class "Default")
      (node (ref "CON4") (pin "76") (pinfunction "76_76") (pintype "passive"))
    )
    (net (code "98") (name "/HDMI0_TX2_N") (class "Default")
      (node (ref "CON4") (pin "72") (pinfunction "72_72") (pintype "passive"))
    )
    (net (code "99") (name "/HDMI0_TX2_P") (class "Default")
      (node (ref "CON4") (pin "70") (pinfunction "70_70") (pintype "passive"))
    )
    (net (code "100") (name "/HDMI1_CEC") (class "Default")
      (node (ref "CON4") (pin "49") (pinfunction "49_49") (pintype "passive"))
    )
    (net (code "101") (name "/HDMI1_CLK_N") (class "Default")
      (node (ref "CON4") (pin "66") (pinfunction "66_66") (pintype "passive"))
    )
    (net (code "102") (name "/HDMI1_CLK_P") (class "Default")
      (node (ref "CON4") (pin "64") (pinfunction "64_64") (pintype "passive"))
    )
    (net (code "103") (name "/HDMI1_HOTPLUG") (class "Default")
      (node (ref "CON4") (pin "43") (pinfunction "43_43") (pintype "passive"))
    )
    (net (code "104") (name "/HDMI1_SCL") (class "Default")
      (node (ref "CON4") (pin "47") (pinfunction "47_47") (pintype "passive"))
    )
    (net (code "105") (name "/HDMI1_SDA") (class "Default")
      (node (ref "CON4") (pin "45") (pinfunction "45_45") (pintype "passive"))
    )
    (net (code "106") (name "/HDMI1_TX0_N") (class "Default")
      (node (ref "CON4") (pin "60") (pinfunction "60_60") (pintype "passive"))
    )
    (net (code "107") (name "/HDMI1_TX0_P") (class "Default")
      (node (ref "CON4") (pin "58") (pinfunction "58_58") (pintype "passive"))
    )
    (net (code "108") (name "/HDMI1_TX1_N") (class "Default")
      (node (ref "CON4") (pin "54") (pinfunction "54_54") (pintype "passive"))
    )
    (net (code "109") (name "/HDMI1_TX1_P") (class "Default")
      (node (ref "CON4") (pin "52") (pinfunction "52_52") (pintype "passive"))
    )
    (net (code "110") (name "/HDMI1_TX2_N") (class "Default")
      (node (ref "CON4") (pin "48") (pinfunction "48_48") (pintype "passive"))
    )
    (net (code "111") (name "/HDMI1_TX2_P") (class "Default")
      (node (ref "CON4") (pin "46") (pinfunction "46_46") (pintype "passive"))
    )
    (net (code "112") (name "/ID_SC") (class "Default")
      (node (ref "CON3") (pin "35") (pinfunction "35_35") (pintype "passive"))
    )
    (net (code "113") (name "/ID_SD") (class "Default")
      (node (ref "CON3") (pin "36") (pinfunction "36_36") (pintype "passive"))
    )
    (net (code "114") (name "/PCIe_CLK_N") (class "Default")
      (node (ref "CON4") (pin "12") (pinfunction "12_12") (pintype "passive"))
    )
    (net (code "115") (name "/PCIe_CLK_P") (class "Default")
      (node (ref "CON4") (pin "10") (pinfunction "10_10") (pintype "passive"))
    )
    (net (code "116") (name "/PCIe_CLK_nREQ") (class "Default")
      (node (ref "CON4") (pin "2") (pinfunction "2_2") (pintype "passive"))
    )
    (net (code "117") (name "/PCIe_RX_N") (class "Default")
      (node (ref "CON4") (pin "18") (pinfunction "18_18") (pintype "passive"))
    )
    (net (code "118") (name "/PCIe_RX_P") (class "Default")
      (node (ref "CON4") (pin "16") (pinfunction "16_16") (pintype "passive"))
    )
    (net (code "119") (name "/PCIe_TX_N") (class "Default")
      (node (ref "CON4") (pin "24") (pinfunction "24_24") (pintype "passive"))
    )
    (net (code "120") (name "/PCIe_TX_P") (class "Default")
      (node (ref "CON4") (pin "22") (pinfunction "22_22") (pintype "passive"))
    )
    (net (code "121") (name "/PCIe_nRST") (class "Default")
      (node (ref "CON4") (pin "9") (pinfunction "9_9") (pintype "passive"))
    )
    (net (code "122") (name "/PI_LED_nPWR") (class "Default")
      (node (ref "CON3") (pin "95") (pinfunction "95_95") (pintype "passive"))
      (node (ref "IC13") (pin "2") (pinfunction "A_2") (pintype "input"))
    )
    (net (code "123") (name "/Pi_nLED_Activity") (class "Default")
      (node (ref "CON3") (pin "21") (pinfunction "21_21") (pintype "passive"))
      (node (ref "R48") (pin "1") (pinfunction "1_1") (pintype "passive"))
    )
    (net (code "124") (name "/RUN_PG") (class "Default")
      (node (ref "CON3") (pin "92") (pinfunction "92_92") (pintype "passive"))
      (node (ref "IC12") (pin "2") (pinfunction "A_2") (pintype "input"))
      (node (ref "J19") (pin "1") (pinfunction "1_1") (pintype "passive"))
      (node (ref "R44") (pin "1") (pinfunction "1_1") (pintype "passive"))
    )
    (net (code "125") (name "/Reserved_1") (class "Default")
      (node (ref "CON3") (pin "76") (pinfunction "76_76") (pintype "passive"))
    )
    (net (code "126") (name "/Reserved_2") (class "Default")
      (node (ref "CON4") (pin "4") (pinfunction "4_4") (pintype "passive"))
    )
    (net (code "127") (name "/Reserved_3") (class "Default")
      (node (ref "CON4") (pin "6") (pinfunction "6_6") (pintype "passive"))
    )
    (net (code "128") (name "/SCL0") (class "Default")
      (node (ref "CON3") (pin "80") (pinfunction "80_80") (pintype "passive"))
      (node (ref "J14") (pin "20") (pinfunction "20_20") (pintype "passive"))
      (node (ref "J15") (pin "20") (pinfunction "20_20") (pintype "passive"))
    )
    (net (code "129") (name "/SDA0") (class "Default")
      (node (ref "CON3") (pin "82") (pinfunction "82_82") (pintype "passive"))
      (node (ref "J14") (pin "21") (pinfunction "21_21") (pintype "passive"))
      (node (ref "J15") (pin "21") (pinfunction "21_21") (pintype "passive"))
    )
    (net (code "130") (name "/SD_CLK") (class "Default")
      (node (ref "CON3") (pin "57") (pinfunction "57_57") (pintype "passive"))
    )
    (net (code "131") (name "/SD_CMD") (class "Default")
      (node (ref "CON3") (pin "62") (pinfunction "62_62") (pintype "passive"))
    )
    (net (code "132") (name "/SD_DAT0") (class "Default")
      (node (ref "CON3") (pin "63") (pinfunction "63_63") (pintype "passive"))
    )
    (net (code "133") (name "/SD_DAT1") (class "Default")
      (node (ref "CON3") (pin "67") (pinfunction "67_67") (pintype "passive"))
    )
    (net (code "134") (name "/SD_DAT2") (class "Default")
      (node (ref "CON3") (pin "69") (pinfunction "69_69") (pintype "passive"))
    )
    (net (code "135") (name "/SD_DAT3") (class "Default")
      (node (ref "CON3") (pin "61") (pinfunction "61_61") (pintype "passive"))
    )
    (net (code "136") (name "/SD_DAT4") (class "Default")
      (node (ref "CON3") (pin "68") (pinfunction "68_68") (pintype "passive"))
    )
    (net (code "137") (name "/SD_DAT5") (class "Default")
      (node (ref "CON3") (pin "64") (pinfunction "64_64") (pintype "passive"))
    )
    (net (code "138") (name "/SD_DAT6") (class "Default")
      (node (ref "CON3") (pin "72") (pinfunction "72_72") (pintype "passive"))
    )
    (net (code "139") (name "/SD_DAT7") (class "Default")
      (node (ref "CON3") (pin "70") (pinfunction "70_70") (pintype "passive"))
    )
    (net (code "140") (name "/SD_PWR_ON") (class "Default")
      (node (ref "CON3") (pin "75") (pinfunction "75_75") (pintype "passive"))
    )
    (net (code "141") (name "/SD_VDD_Override") (class "Default")
      (node (ref "CON3") (pin "73") (pinfunction "73_73") (pintype "passive"))
    )
    (net (code "142") (name "/USB_N") (class "Default")
      (node (ref "CON4") (pin "3") (pinfunction "3_3") (pintype "passive"))
    )
    (net (code "143") (name "/USB_OTG_ID") (class "Default")
      (node (ref "CON4") (pin "1") (pinfunction "1_1") (pintype "passive"))
    )
    (net (code "144") (name "/USB_P") (class "Default")
      (node (ref "CON4") (pin "5") (pinfunction "5_5") (pintype "passive"))
    )
    (net (code "145") (name "/VDAC_COMP") (class "Default")
      (node (ref "CON4") (pin "11") (pinfunction "11_11") (pintype "passive"))
    )
    (net (code "146") (name "/WL_nDisable") (class "Default")
      (node (ref "CON3") (pin "89") (pinfunction "89_89") (pintype "passive"))
      (node (ref "R40") (pin "2") (pinfunction "2_2") (pintype "passive"))
    )
    (net (code "147") (name "/nEXTRST") (class "Default")
      (node (ref "CON3") (pin "100") (pinfunction "100_100") (pintype "passive"))
    )
    (net (code "148") (name "/nRPIBOOT") (class "Default")
      (node (ref "CON3") (pin "93") (pinfunction "93_93") (pintype "passive"))
      (node (ref "J17") (pin "1") (pinfunction "1_1") (pintype "passive"))
    )
    (net (code "154") (name "CHASSIS") (class "Default")
      (node (ref "CON5") (pin "Shell") (pinfunction "Shield_Shell") (pintype "passive"))
      (node (ref "SW1") (pin "3") (pinfunction "3_3") (pintype "passive"))
      (node (ref "SW2") (pin "3") (pinfunction "3_3") (pintype "passive"))
    )
    (net (code "155") (name "GND") (class "Default")
      (node (ref "C43") (pin "2") (pintype "passive"))
      (node (ref "CON3") (pin "1") (pinfunction "1_1") (pintype "passive"))
      (node (ref "CON3") (pin "13") (pinfunction "13_13") (pintype "passive"))
      (node (ref "CON3") (pin "14") (pinfunction "14_14") (pintype "passive"))
      (node (ref "CON3") (pin "2") (pinfunction "2_2") (pintype "passive"))
      (node (ref "CON3") (pin "22") (pinfunction "22_22") (pintype "passive"))
      (node (ref "CON3") (pin "23") (pinfunction "23_23") (pintype "passive"))
      (node (ref "CON3") (pin "32") (pinfunction "32_32") (pintype "passive"))
      (node (ref "CON3") (pin "33") (pinfunction "33_33") (pintype "passive"))
      (node (ref "CON3") (pin "42") (pinfunction "42_42") (pintype "passive"))
      (node (ref "CON3") (pin "43") (pinfunction "43_43") (pintype "passive"))
      (node (ref "CON3") (pin "52") (pinfunction "52_52") (pintype "passive"))
      (node (ref "CON3") (pin "53") (pinfunction "53_53") (pintype "passive"))
      (node (ref "CON3") (pin "59") (pinfunction "59_59") (pintype "passive"))
      (node (ref "CON3") (pin "60") (pinfunction "60_60") (pintype "passive"))
      (node (ref "CON3") (pin "65") (pinfunction "65_65") (pintype "passive"))
      (node (ref "CON3") (pin "66") (pinfunction "66_66") (pintype "passive"))
      (node (ref "CON3") (pin "7") (pinfunction "7_7") (pintype "passive"))
      (node (ref "CON3") (pin "71") (pinfunction "71_71") (pintype "passive"))
      (node (ref "CON3") (pin "74") (pinfunction "74_74") (pintype "passive"))
      (node (ref "CON3") (pin "8") (pinfunction "8_8") (pintype "passive"))
      (node (ref "CON3") (pin "98") (pinfunction "98_98") (pintype "passive"))
      (node (ref "CON4") (pin "13") (pinfunction "13_13") (pintype "passive"))
      (node (ref "CON4") (pin "14") (pinfunction "14_14") (pintype "passive"))
      (node (ref "CON4") (pin "19") (pinfunction "19_19") (pintype "passive"))
      (node (ref "CON4") (pin "20") (pinfunction "20_20") (pintype "passive"))
      (node (ref "CON4") (pin "25") (pinfunction "25_25") (pintype "passive"))
      (node (ref "CON4") (pin "26") (pinfunction "26_26") (pintype "passive"))
      (node (ref "CON4") (pin "31") (pinfunction "31_31") (pintype "passive"))
      (node (ref "CON4") (pin "32") (pinfunction "32_32") (pintype "passive"))
      (node (ref "CON4") (pin "37") (pinfunction "37_37") (pintype "passive"))
      (node (ref "CON4") (pin "38") (pinfunction "38_38") (pintype "passive"))
      (node (ref "CON4") (pin "44") (pinfunction "44_44") (pintype "passive"))
      (node (ref "CON4") (pin "50") (pinfunction "50_50") (pintype "passive"))
      (node (ref "CON4") (pin "55") (pinfunction "55_55") (pintype "passive"))
      (node (ref "CON4") (pin "56") (pinfunction "56_56") (pintype "passive"))
      (node (ref "CON4") (pin "61") (pinfunction "61_61") (pintype "passive"))
      (node (ref "CON4") (pin "62") (pinfunction "62_62") (pintype "passive"))
      (node (ref "CON4") (pin "67") (pinfunction "67_67") (pintype "passive"))
      (node (ref "CON4") (pin "68") (pinfunction "68_68") (pintype "passive"))
      (node (ref "CON4") (pin "7") (pinfunction "7_7") (pintype "passive"))
      (node (ref "CON4") (pin "73") (pinfunction "73_73") (pintype "passive"))
      (node (ref "CON4") (pin "74") (pinfunction "74_74") (pintype "passive"))
      (node (ref "CON4") (pin "79") (pinfunction "79_79") (pintype "passive"))
      (node (ref "CON4") (pin "8") (pinfunction "8_8") (pintype "passive"))
      (node (ref "CON4") (pin "80") (pinfunction "80_80") (pintype "passive"))
      (node (ref "CON4") (pin "85") (pinfunction "85_85") (pintype "passive"))
      (node (ref "CON4") (pin "86") (pinfunction "86_86") (pintype "passive"))
      (node (ref "CON4") (pin "91") (pinfunction "91_91") (pintype "passive"))
      (node (ref "CON4") (pin "92") (pinfunction "92_92") (pintype "passive"))
      (node (ref "CON4") (pin "97") (pinfunction "97_97") (pintype "passive"))
      (node (ref "CON4") (pin "98") (pinfunction "98_98") (pintype "passive"))
      (node (ref "CON6") (pin "10") (pinfunction "10_10") (pintype "passive"))
      (node (ref "IC12") (pin "3") (pinfunction "GND_3") (pintype "power_in"))
      (node (ref "IC13") (pin "3") (pinfunction "GND_3") (pintype "power_in"))
      (node (ref "J14") (pin "1") (pinfunction "1_1") (pintype "passive"))
      (node (ref "J14") (pin "10") (pinfunction "10_10") (pintype "passive"))
      (node (ref "J14") (pin "13") (pinfunction "13_13") (pintype "passive"))
      (node (ref "J14") (pin "16") (pinfunction "16_16") (pintype "passive"))
      (node (ref "J14") (pin "19") (pinfunction "19_19") (pintype "passive"))
      (node (ref "J14") (pin "4") (pinfunction "4_4") (pintype "passive"))
      (node (ref "J14") (pin "7") (pinfunction "7_7") (pintype "passive"))
      (node (ref "J14") (pin "MP1") (pinfunction "MP1_MP1") (pintype "passive"))
      (node (ref "J14") (pin "MP2") (pinfunction "MP2_MP2") (pintype "passive"))
      (node (ref "J14") (pin "MP3") (pinfunction "MP3_MP3") (pintype "passive"))
      (node (ref "J14") (pin "MP4") (pinfunction "MP4_MP4") (pintype "passive"))
      (node (ref "J15") (pin "1") (pinfunction "1_1") (pintype "passive"))
      (node (ref "J15") (pin "10") (pinfunction "10_10") (pintype "passive"))
      (node (ref "J15") (pin "13") (pinfunction "13_13") (pintype "passive"))
      (node (ref "J15") (pin "16") (pinfunction "16_16") (pintype "passive"))
      (node (ref "J15") (pin "19") (pinfunction "19_19") (pintype "passive"))
      (node (ref "J15") (pin "4") (pinfunction "4_4") (pintype "passive"))
      (node (ref "J15") (pin "7") (pinfunction "7_7") (pintype "passive"))
      (node (ref "J15") (pin "MP1") (pinfunction "MP1_MP1") (pintype "passive"))
      (node (ref "J15") (pin "MP2") (pinfunction "MP2_MP2") (pintype "passive"))
      (node (ref "J15") (pin "MP3") (pinfunction "MP3_MP3") (pintype "passive"))
      (node (ref "J15") (pin "MP4") (pinfunction "MP4_MP4") (pintype "passive"))
      (node (ref "J16") (pin "2") (pinfunction "2_2") (pintype "passive"))
      (node (ref "J17") (pin "2") (pinfunction "2_2") (pintype "passive"))
      (node (ref "J18") (pin "2") (pinfunction "2_2") (pintype "passive"))
      (node (ref "J19") (pin "2") (pinfunction "2_2") (pintype "passive"))
      (node (ref "J20") (pin "3") (pinfunction "3_3") (pintype "passive"))
      (node (ref "J20") (pin "4") (pinfunction "4_4") (pintype "passive"))
      (node (ref "R38") (pin "2") (pinfunction "2_2") (pintype "passive"))
      (node (ref "R39") (pin "2") (pinfunction "2_2") (pintype "passive"))
      (node (ref "R40") (pin "1") (pinfunction "1_1") (pintype "passive"))
      (node (ref "R41") (pin "1") (pinfunction "1_1") (pintype "passive"))
      (node (ref "R46") (pin "2") (pinfunction "2_2") (pintype "passive"))
      (node (ref "R88") (pin "1") (pinfunction "1_1") (pintype "passive"))
      (node (ref "R89") (pin "1") (pinfunction "1_1") (pintype "passive"))
      (node (ref "TP5") (pin "1") (pinfunction "1_1") (pintype "passive"))
      (node (ref "TR3") (pin "2") (pinfunction "E_2") (pintype "passive"))
      (node (ref "TR7") (pin "2") (pinfunction "E_2") (pintype "passive"))
      (node (ref "TR8") (pin "2") (pinfunction "E_2") (pintype "passive"))
      (node (ref "TVS12") (pin "3") (pinfunction "GND_3") (pintype "passive"))
    )
    (net (code "156") (name "Net-(C43-Pad1)") (class "Default")
      (node (ref "C43") (pin "1") (pintype "passive"))
      (node (ref "CON5") (pin "5") (pinfunction "VCC/GND_5") (pintype "passive"))
      (node (ref "CON5") (pin "6") (pinfunction "VCC/GND_6") (pintype "passive"))
    )
    (net (code "157") (name "Net-(CON5-Pad12)") (class "Default")
      (node (ref "CON5") (pin "12") (pinfunction "12_12") (pintype "passive"))
      (node (ref "R38") (pin "1") (pinfunction "1_1") (pintype "passive"))
    )
    (net (code "158") (name "Net-(CON5-Pad13)") (class "Default")
      (node (ref "CON5") (pin "13") (pinfunction "13_13") (pintype "passive"))
      (node (ref "R39") (pin "1") (pinfunction "1_1") (pintype "passive"))
    )
    (net (code "159") (name "Net-(IC12-Y)") (class "Default")
      (node (ref "IC12") (pin "4") (pinfunction "Y_4") (pintype "output"))
      (node (ref "SW1") (pin "1") (pinfunction "1_1") (pintype "passive"))
    )
    (net (code "160") (name "Net-(IC13-Y)") (class "Default")
      (node (ref "IC13") (pin "4") (pinfunction "Y_4") (pintype "output"))
      (node (ref "R47") (pin "2") (pinfunction "2_2") (pintype "passive"))
    )
    (net (code "161") (name "Net-(LED1-Pad2)") (class "Default")
      (node (ref "LED1") (pin "2") (pinfunction "2_2") (pintype "passive"))
      (node (ref "R47") (pin "1") (pinfunction "1_1") (pintype "passive"))
    )
    (net (code "162") (name "Net-(LED2-Pad2)") (class "Default")
      (node (ref "LED2") (pin "2") (pinfunction "2_2") (pintype "passive"))
      (node (ref "R48") (pin "2") (pinfunction "2_2") (pintype "passive"))
    )
    (net (code "163") (name "Net-(LED5-Pad2)") (class "Default")
      (node (ref "LED5") (pin "2") (pinfunction "2_2") (pintype "passive"))
      (node (ref "R43") (pin "2") (pinfunction "2_2") (pintype "passive"))
    )
    (net (code "164") (name "Net-(LED6-Pad2)") (class "Default")
      (node (ref "LED6") (pin "2") (pinfunction "2_2") (pintype "passive"))
      (node (ref "R63") (pin "2") (pinfunction "2_2") (pintype "passive"))
    )
    (net (code "165") (name "Net-(R45-Pad2)") (class "Default")
      (node (ref "R45") (pin "2") (pinfunction "2_2") (pintype "passive"))
      (node (ref "SW2") (pin "2") (pinfunction "2_2") (pintype "passive"))
    )
    (net (code "166") (name "Net-(TR3-B)") (class "Default")
      (node (ref "R45") (pin "1") (pinfunction "1_1") (pintype "passive"))
      (node (ref "R46") (pin "1") (pinfunction "1_1") (pintype "passive"))
      (node (ref "TR3") (pin "1") (pinfunction "B_1") (pintype "passive"))
    )
    (net (code "167") (name "Net-(TR3-C)") (class "Default")
      (node (ref "R44") (pin "2") (pinfunction "2_2") (pintype "passive"))
      (node (ref "TR3") (pin "3") (pinfunction "C_3") (pintype "passive"))
    )
    (net (code "168") (name "Net-(TR7-B)") (class "Default")
      (node (ref "R64") (pin "2") (pinfunction "2_2") (pintype "passive"))
      (node (ref "R88") (pin "2") (pinfunction "2_2") (pintype "passive"))
      (node (ref "TR7") (pin "1") (pinfunction "B_1") (pintype "passive"))
    )
    (net (code "169") (name "Net-(TR7-C)") (class "Default")
      (node (ref "R43") (pin "1") (pinfunction "1_1") (pintype "passive"))
      (node (ref "TR7") (pin "3") (pinfunction "C_3") (pintype "passive"))
    )
    (net (code "170") (name "Net-(TR8-B)") (class "Default")
      (node (ref "R68") (pin "2") (pinfunction "2_2") (pintype "passive"))
      (node (ref "R89") (pin "2") (pinfunction "2_2") (pintype "passive"))
      (node (ref "TR8") (pin "1") (pinfunction "B_1") (pintype "passive"))
    )
    (net (code "171") (name "Net-(TR8-C)") (class "Default")
      (node (ref "R63") (pin "1") (pinfunction "1_1") (pintype "passive"))
      (node (ref "TR8") (pin "3") (pinfunction "C_3") (pintype "passive"))
    )
    (net (code "172") (name "unconnected-(CON6-Pad4)") (class "Default")
      (node (ref "CON6") (pin "4") (pinfunction "4_4") (pintype "passive"))
    )
    (net (code "173") (name "unconnected-(IC12-NC-Pad1)") (class "Default")
      (node (ref "IC12") (pin "1") (pinfunction "NC_1") (pintype "input+no_connect"))
    )
    (net (code "174") (name "unconnected-(IC13-NC-Pad1)") (class "Default")
      (node (ref "IC13") (pin "1") (pinfunction "NC_1") (pintype "input+no_connect"))
    )
    (net (code "175") (name "unconnected-(J14-Pad18)") (class "Default")
      (node (ref "J14") (pin "18") (pinfunction "18_18") (pintype "passive+no_connect"))
    )
    (net (code "176") (name "unconnected-(J15-Pad17)") (class "Default")
      (node (ref "J15") (pin "17") (pinfunction "17_17") (pintype "passive+no_connect"))
    )
    (net (code "177") (name "unconnected-(J15-Pad18)") (class "Default")
      (node (ref "J15") (pin "18") (pinfunction "18_18") (pintype "passive+no_connect"))
    )
  )
)
